# EMU_comp.net
KiCad netlist of a schematic drawn in Altium Designer
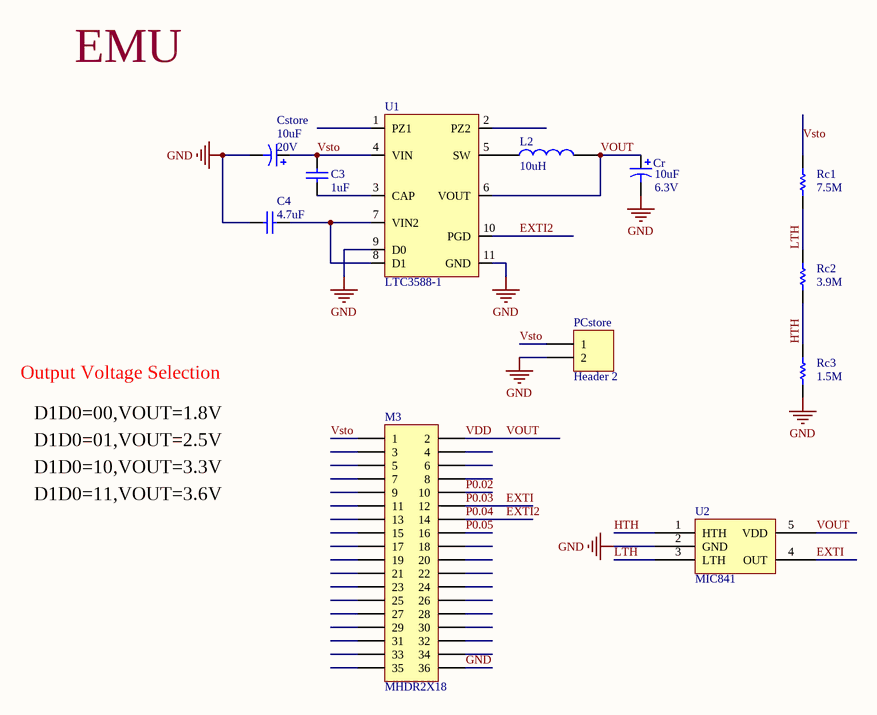
[diagram p0: EMU_comp.SchDoc]

(export (version "E")
  (design (tool "Eeschema 10.0.6"))
  (components
    (comp (ref "C3")
      (value "1uF")
      (footprint "6-0805_N")
      (description "Capacitor")
      (fields (field (name "Comment") "CAP") (field (name "PUBLISHER") "Altium Limited"))
      (libsource (lib "Harry_PCBLib") (part "Cap"))
    )
    (comp (ref "C4")
      (value "4.7uF")
      (footprint "6-0805_N")
      (description "Capacitor")
      (fields (field (name "Comment") "CAP") (field (name "PUBLISHER") "Altium Limited"))
      (libsource (lib "Harry_PCBLib") (part "Cap"))
    )
    (comp (ref "Cr")
      (value "6.3V")
      (footprint "3216[1206]")
      (description "Polarized Capacitor (Radial)")
      (fields (field (name "ALTIUM_VALUE") "10uF") (field (name "PUBLISHER") "Altium Limited"))
      (libsource (lib "Miscellaneous Devices") (part "Cap Pol1"))
    )
    (comp (ref "Cstore")
      (value "10uF")
      (footprint "钽电容")
      (description "Polarized Capacitor (Radial)")
      (fields
        (field (name "NOMINAL VOLTAGE") "20V")
        (field (name "Comment") "Cap Pol1")
        (field (name "PUBLISHER") "Altium Limited")
      )
      (libsource (lib "Miscellaneous Devices") (part "Cap Pol1"))
    )
    (comp (ref "L2") (value "10uH") (footprint "inductor") (libsource (lib "Harry_PCBLib") (part "INDUCTOR")))
    (comp (ref "M3")
      (value "MHDR2X18")
      (footprint "header:module9x4")
      (description "Header, 18-Pin, Dual row")
      (fields (field (name "PUBLISHER") "Altium Limited"))
      (libsource (lib "Miscellaneous Connectors") (part "MHDR2X18"))
    )
    (comp (ref "PCstore")
      (value "Header 2")
      (footprint "HDR1X2")
      (description "Header, 2-Pin")
      (fields (field (name "PUBLISHER") "Altium Limited"))
      (libsource (lib "Miscellaneous Connectors") (part "Header 2"))
    )
    (comp (ref "Rc1")
      (value "7.5M")
      (footprint "6-0805_N")
      (description "Resistor")
      (fields (field (name "Comment") "Res1") (field (name "PUBLISHER") "Altium Limited"))
      (libsource (lib "Miscellaneous Devices") (part "Res1"))
    )
    (comp (ref "Rc2")
      (value "3.9M")
      (footprint "6-0805_N")
      (description "Resistor")
      (fields (field (name "Comment") "Res1") (field (name "PUBLISHER") "Altium Limited"))
      (libsource (lib "Miscellaneous Devices") (part "Res1"))
    )
    (comp (ref "Rc3")
      (value "1.5M")
      (footprint "6-0805_N")
      (description "Resistor")
      (fields (field (name "Comment") "Res1") (field (name "PUBLISHER") "Altium Limited"))
      (libsource (lib "Miscellaneous Devices") (part "Res1"))
    )
    (comp (ref "U1")
      (value "LTC3588-1")
      (footprint "LTC 3588-1")
      (description "Nanopower energy harvesting power supply")
      (libsource (lib "Self-power SSHI") (part "LTC3588-1"))
    )
    (comp (ref "U2")
      (value "MIC841")
      (footprint "PcbLib1:MIC841")
      (libsource (lib "MIC841") (part "Component_1"))
    )
  )
  (nets
    (net (code "1") (name "/EXTI") (class "Default")
      (node (ref "M3") (pin "12") (pinfunction "12_12") (pintype "passive"))
      (node (ref "U2") (pin "4") (pinfunction "OUT_4") (pintype "passive"))
    )
    (net (code "2") (name "/EXTI2") (class "Default")
      (node (ref "M3") (pin "14") (pinfunction "14_14") (pintype "passive"))
      (node (ref "U1") (pin "10") (pinfunction "PGD_10") (pintype "passive"))
    )
    (net (code "3") (name "/HTH") (class "Default")
      (node (ref "Rc2") (pin "1") (pinfunction "1_1") (pintype "passive"))
      (node (ref "Rc3") (pin "2") (pinfunction "2_2") (pintype "passive"))
      (node (ref "U2") (pin "1") (pinfunction "HTH_1") (pintype "passive"))
    )
    (net (code "4") (name "/LTH") (class "Default")
      (node (ref "Rc1") (pin "1") (pinfunction "1_1") (pintype "passive"))
      (node (ref "Rc2") (pin "2") (pinfunction "2_2") (pintype "passive"))
      (node (ref "U2") (pin "3") (pinfunction "LTH_3") (pintype "passive"))
    )
    (net (code "5") (name "/P0.02") (class "Default")
      (node (ref "M3") (pin "10") (pinfunction "10_10") (pintype "passive"))
    )
    (net (code "6") (name "/P0.05") (class "Default")
      (node (ref "M3") (pin "16") (pinfunction "16_16") (pintype "passive"))
    )
    (net (code "7") (name "/VDD") (class "Default")
      (node (ref "Cr") (pin "1") (pinfunction "1_1") (pintype "passive"))
      (node (ref "L2") (pin "2") (pinfunction "2_2") (pintype "passive"))
      (node (ref "M3") (pin "2") (pinfunction "2_2") (pintype "passive"))
      (node (ref "U1") (pin "6") (pinfunction "VOUT_6") (pintype "passive"))
      (node (ref "U2") (pin "5") (pinfunction "VDD_5") (pintype "passive"))
    )
    (net (code "8") (name "/Vsto") (class "Default")
      (node (ref "C3") (pin "2") (pinfunction "2_2") (pintype "passive"))
      (node (ref "Cstore") (pin "1") (pinfunction "1_1") (pintype "passive"))
      (node (ref "M3") (pin "1") (pinfunction "1_1") (pintype "passive"))
      (node (ref "PCstore") (pin "1") (pinfunction "1_1") (pintype "passive"))
      (node (ref "Rc1") (pin "2") (pinfunction "2_2") (pintype "passive"))
      (node (ref "U1") (pin "4") (pinfunction "VIN_4") (pintype "passive"))
    )
    (net (code "9") (name "GND") (class "Default")
      (node (ref "C4") (pin "2") (pinfunction "2_2") (pintype "passive"))
      (node (ref "Cr") (pin "2") (pinfunction "2_2") (pintype "passive"))
      (node (ref "Cstore") (pin "2") (pinfunction "2_2") (pintype "passive"))
      (node (ref "M3") (pin "36") (pinfunction "36_36") (pintype "passive"))
      (node (ref "PCstore") (pin "2") (pinfunction "2_2") (pintype "passive"))
      (node (ref "Rc3") (pin "1") (pinfunction "1_1") (pintype "passive"))
      (node (ref "U1") (pin "11") (pinfunction "GND_11") (pintype "passive"))
      (node (ref "U1") (pin "9") (pinfunction "D0_9") (pintype "passive"))
      (node (ref "U2") (pin "2") (pinfunction "GND_2") (pintype "passive"))
    )
    (net (code "10") (name "Net-(U1-CAP)") (class "Default")
      (node (ref "C3") (pin "1") (pinfunction "1_1") (pintype "passive"))
      (node (ref "U1") (pin "3") (pinfunction "CAP_3") (pintype "passive"))
    )
    (net (code "11") (name "Net-(U1-D1)") (class "Default")
      (node (ref "C4") (pin "1") (pinfunction "1_1") (pintype "passive"))
      (node (ref "U1") (pin "7") (pinfunction "VIN2_7") (pintype "passive"))
      (node (ref "U1") (pin "8") (pinfunction "D1_8") (pintype "passive"))
    )
    (net (code "12") (name "Net-(U1-SW)") (class "Default")
      (node (ref "L2") (pin "1") (pinfunction "1_1") (pintype "passive"))
      (node (ref "U1") (pin "5") (pinfunction "SW_5") (pintype "passive"))
    )
    (net (code "13") (name "unconnected-(M3-Pad3)") (class "Default")
      (node (ref "M3") (pin "3") (pinfunction "3_3") (pintype "passive"))
    )
    (net (code "14") (name "unconnected-(M3-Pad4)") (class "Default")
      (node (ref "M3") (pin "4") (pinfunction "4_4") (pintype "passive"))
    )
    (net (code "15") (name "unconnected-(M3-Pad5)") (class "Default")
      (node (ref "M3") (pin "5") (pinfunction "5_5") (pintype "passive"))
    )
    (net (code "16") (name "unconnected-(M3-Pad6)") (class "Default")
      (node (ref "M3") (pin "6") (pinfunction "6_6") (pintype "passive"))
    )
    (net (code "17") (name "unconnected-(M3-Pad7)") (class "Default")
      (node (ref "M3") (pin "7") (pinfunction "7_7") (pintype "passive"))
    )
    (net (code "18") (name "unconnected-(M3-Pad8)") (class "Default")
      (node (ref "M3") (pin "8") (pinfunction "8_8") (pintype "passive"))
    )
    (net (code "19") (name "unconnected-(M3-Pad9)") (class "Default")
      (node (ref "M3") (pin "9") (pinfunction "9_9") (pintype "passive"))
    )
    (net (code "20") (name "unconnected-(M3-Pad11)") (class "Default")
      (node (ref "M3") (pin "11") (pinfunction "11_11") (pintype "passive"))
    )
    (net (code "21") (name "unconnected-(M3-Pad13)") (class "Default")
      (node (ref "M3") (pin "13") (pinfunction "13_13") (pintype "passive"))
    )
    (net (code "22") (name "unconnected-(M3-Pad15)") (class "Default")
      (node (ref "M3") (pin "15") (pinfunction "15_15") (pintype "passive"))
    )
    (net (code "23") (name "unconnected-(M3-Pad17)") (class "Default")
      (node (ref "M3") (pin "17") (pinfunction "17_17") (pintype "passive"))
    )
    (net (code "24") (name "unconnected-(M3-Pad18)") (class "Default")
      (node (ref "M3") (pin "18") (pinfunction "18_18") (pintype "passive"))
    )
    (net (code "25") (name "unconnected-(M3-Pad19)") (class "Default")
      (node (ref "M3") (pin "19") (pinfunction "19_19") (pintype "passive"))
    )
    (net (code "26") (name "unconnected-(M3-Pad20)") (class "Default")
      (node (ref "M3") (pin "20") (pinfunction "20_20") (pintype "passive"))
    )
    (net (code "27") (name "unconnected-(M3-Pad21)") (class "Default")
      (node (ref "M3") (pin "21") (pinfunction "21_21") (pintype "passive"))
    )
    (net (code "28") (name "unconnected-(M3-Pad22)") (class "Default")
      (node (ref "M3") (pin "22") (pinfunction "22_22") (pintype "passive"))
    )
    (net (code "29") (name "unconnected-(M3-Pad23)") (class "Default")
      (node (ref "M3") (pin "23") (pinfunction "23_23") (pintype "passive"))
    )
    (net (code "30") (name "unconnected-(M3-Pad24)") (class "Default")
      (node (ref "M3") (pin "24") (pinfunction "24_24") (pintype "passive"))
    )
    (net (code "31") (name "unconnected-(M3-Pad25)") (class "Default")
      (node (ref "M3") (pin "25") (pinfunction "25_25") (pintype "passive"))
    )
    (net (code "32") (name "unconnected-(M3-Pad26)") (class "Default")
      (node (ref "M3") (pin "26") (pinfunction "26_26") (pintype "passive"))
    )
    (net (code "33") (name "unconnected-(M3-Pad27)") (class "Default")
      (node (ref "M3") (pin "27") (pinfunction "27_27") (pintype "passive"))
    )
    (net (code "34") (name "unconnected-(M3-Pad28)") (class "Default")
      (node (ref "M3") (pin "28") (pinfunction "28_28") (pintype "passive"))
    )
    (net (code "35") (name "unconnected-(M3-Pad29)") (class "Default")
      (node (ref "M3") (pin "29") (pinfunction "29_29") (pintype "passive"))
    )
    (net (code "36") (name "unconnected-(M3-Pad30)") (class "Default")
      (node (ref "M3") (pin "30") (pinfunction "30_30") (pintype "passive"))
    )
    (net (code "37") (name "unconnected-(M3-Pad31)") (class "Default")
      (node (ref "M3") (pin "31") (pinfunction "31_31") (pintype "passive"))
    )
    (net (code "38") (name "unconnected-(M3-Pad32)") (class "Default")
      (node (ref "M3") (pin "32") (pinfunction "32_32") (pintype "passive"))
    )
    (net (code "39") (name "unconnected-(M3-Pad33)") (class "Default")
      (node (ref "M3") (pin "33") (pinfunction "33_33") (pintype "passive"))
    )
    (net (code "40") (name "unconnected-(M3-Pad34)") (class "Default")
      (node (ref "M3") (pin "34") (pinfunction "34_34") (pintype "passive"))
    )
    (net (code "41") (name "unconnected-(M3-Pad35)") (class "Default")
      (node (ref "M3") (pin "35") (pinfunction "35_35") (pintype "passive"))
    )
    (net (code "42") (name "unconnected-(U1-PZ1-Pad1)") (class "Default")
      (node (ref "U1") (pin "1") (pinfunction "PZ1_1") (pintype "passive"))
    )
    (net (code "43") (name "unconnected-(U1-PZ2-Pad2)") (class "Default")
      (node (ref "U1") (pin "2") (pinfunction "PZ2_2") (pintype "passive"))
    )
  )
)
